# Connectors.net
KiCad netlist of a schematic drawn in Altium Designer
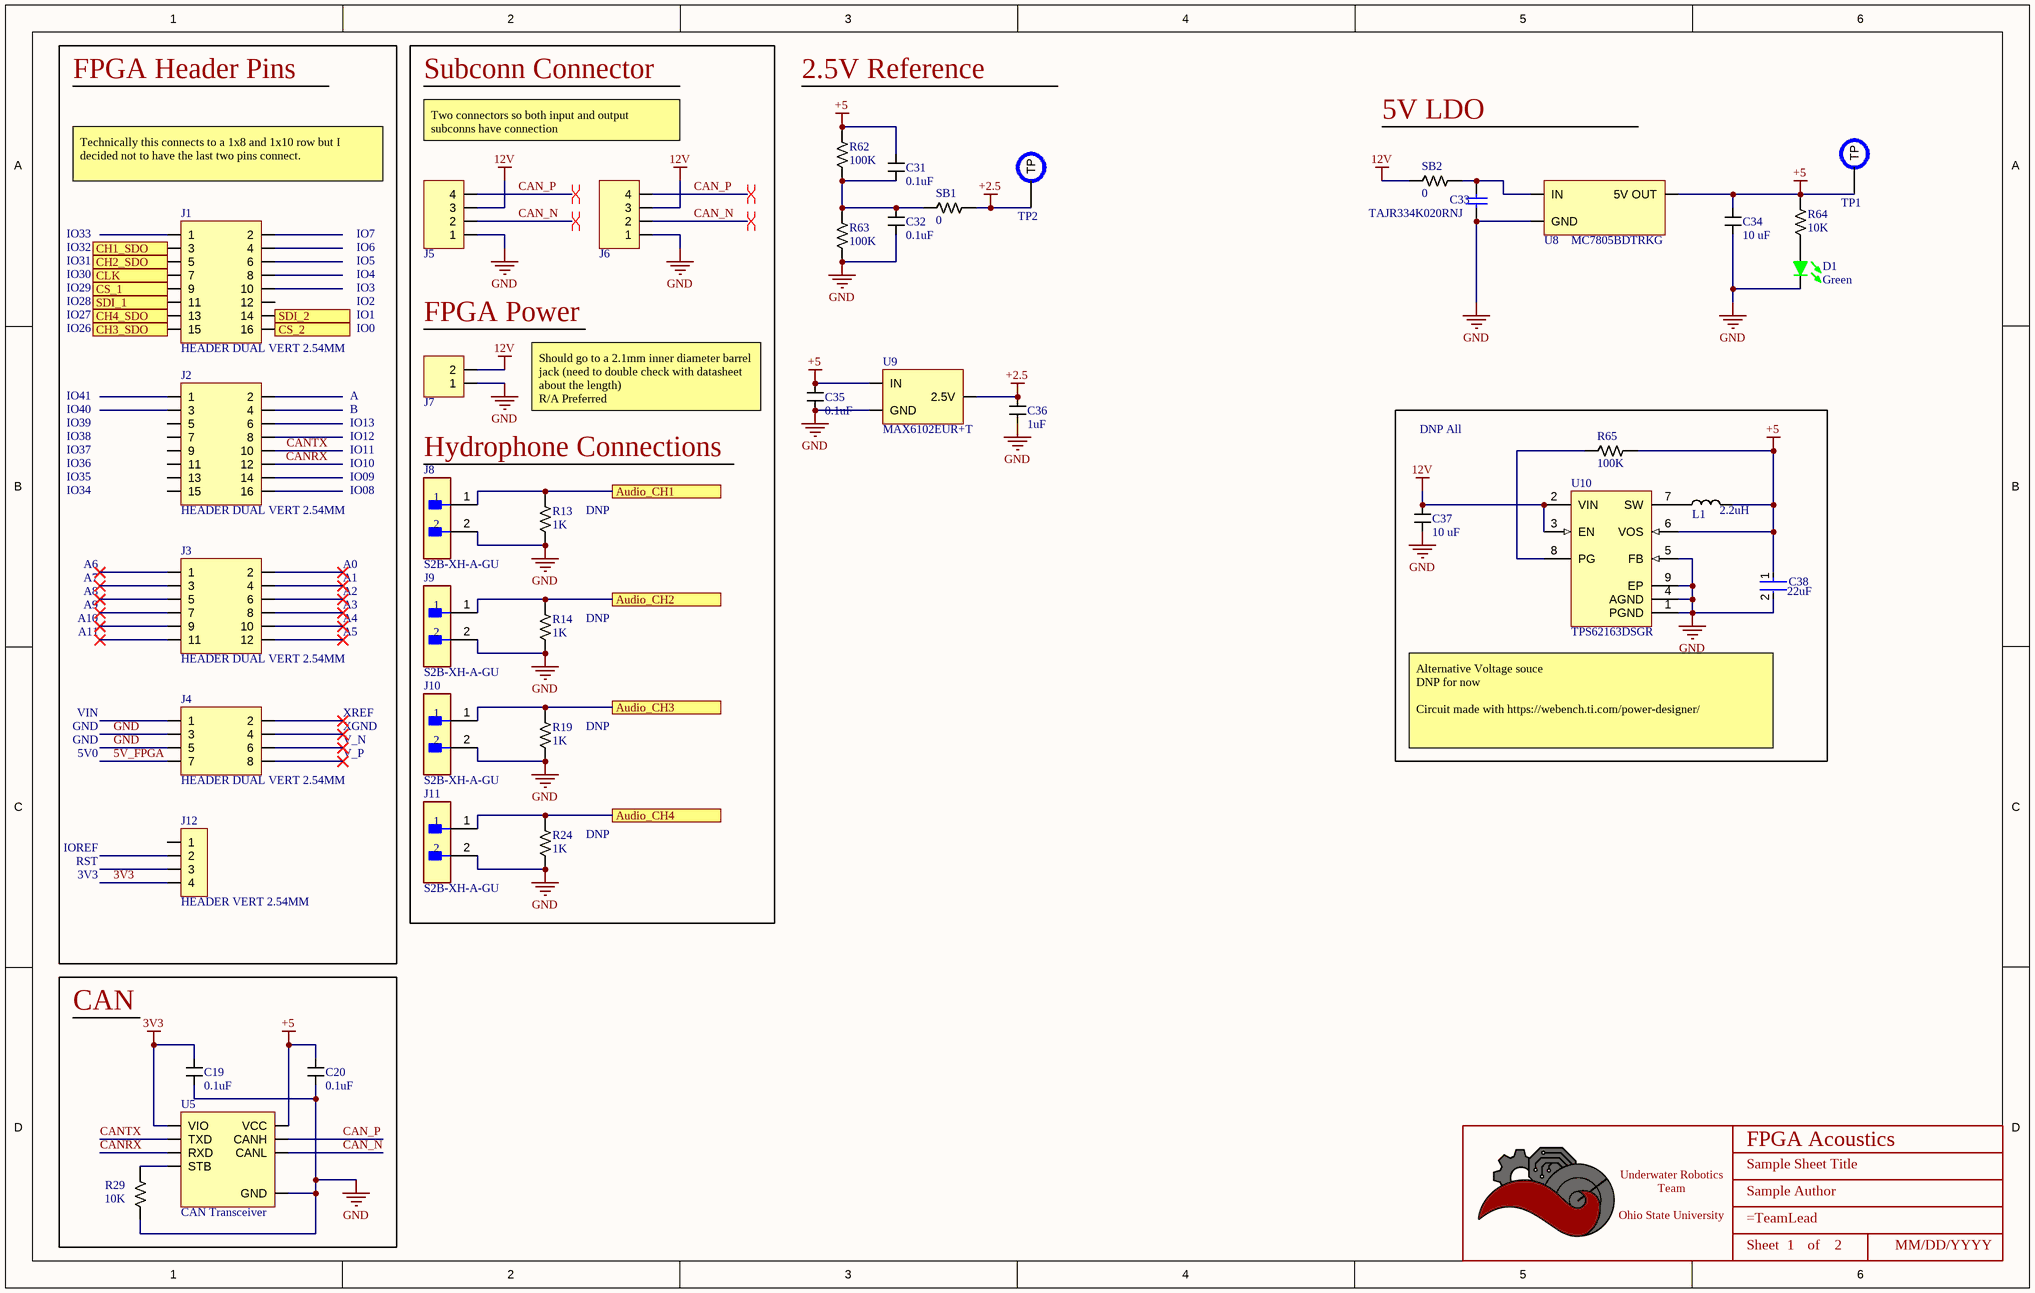
[diagram p0: Connectors.SchDoc]

(export (version "E")
  (design (tool "Eeschema 10.0.6"))
  (components
    (comp (ref "C19")
      (value "0.1uF")
      (footprint "CAPACITOR_0402")
      (description "Cap 100nF 25V +/-10%\r\nCeramic 0402")
      (fields
        (field (name "TOLERANCE") "+/- 10%")
        (field (name "VOLTAGE") "25V")
        (field (name "MADE BY") "Robert Pafford")
      )
      (libsource (lib "Capacitors") (part "CAPACITOR_0.1uF_0402"))
    )
    (comp (ref "C20")
      (value "0.1uF")
      (footprint "CAPACITOR_0402")
      (description "Cap 100nF 25V +/-10%\r\nCeramic 0402")
      (fields
        (field (name "TOLERANCE") "+/- 10%")
        (field (name "VOLTAGE") "25V")
        (field (name "MADE BY") "Robert Pafford")
      )
      (libsource (lib "Capacitors") (part "CAPACITOR_0.1uF_0402"))
    )
    (comp (ref "C31")
      (value "0.1uF")
      (footprint "CAPACITOR_0603")
      (description "Cap 100nF 6.3V +/-10%\r\nCeramic 0603")
      (fields
        (field (name "TOLERANCE") "+/- 10%")
        (field (name "VOLTAGE") "6.3V")
        (field (name "MADE BY") "Flip B")
      )
      (libsource (lib "Capacitors") (part "CAPACITOR_0.1uF_0603"))
    )
    (comp (ref "C32")
      (value "0.1uF")
      (footprint "CAPACITOR_0603")
      (description "Cap 100nF 6.3V +/-10%\r\nCeramic 0603")
      (fields
        (field (name "TOLERANCE") "+/- 10%")
        (field (name "VOLTAGE") "6.3V")
        (field (name "MADE BY") "Flip B")
      )
      (libsource (lib "Capacitors") (part "CAPACITOR_0.1uF_0603"))
    )
    (comp (ref "C33")
      (value "TAJR334K020RNJ")
      (footprint "CAPC2113X120X50NL20T30")
      (fields (field (name "MANUFACTURER") "AVX Interconnect / Elco"))
      (libsource (lib "Altium Content Vault") (part "CAP"))
    )
    (comp (ref "C34")
      (value "10uF Ceramic 6.3V")
      (footprint "CAPACITOR_0603")
      (description "Cap 10uF 6.3V +/-20%\r\nCeramic 0603")
      (fields
        (field (name "TOLERANCE") "+/- 20%")
        (field (name "VOLTAGE") "6.3V")
        (field (name "VALUE (UF)") "10 uF")
        (field (name "MADE BY") "Flip B")
      )
      (libsource (lib "Capacitors") (part "CAPACITOR_10uF_0603"))
    )
    (comp (ref "C35")
      (value "0.1uF")
      (footprint "CAPACITOR_0603")
      (description "Cap 100nF 25V +/-10%\r\nCeramic 0603")
      (fields
        (field (name "TOLERANCE") "+/- 10%")
        (field (name "VOLTAGE") "6.3V")
        (field (name "MADE BY") "Flip B")
      )
      (libsource (lib "Capacitors") (part "CAPACITOR_0.1uF_0603_25V"))
    )
    (comp (ref "C36")
      (value "1uF")
      (footprint "CAPACITOR_0603")
      (description "Cap 1uF 16V +/-10%\r\nCeramic 0603")
      (fields
        (field (name "TOLERANCE") "+/- 10%")
        (field (name "VOLTAGE") "16V")
        (field (name "MADE BY") "Flip B")
      )
      (libsource (lib "Capacitors") (part "CAPACITOR_1uF_0603"))
    )
    (comp (ref "C37")
      (value "10uF Ceramic 25V")
      (footprint "CAPACITOR_1206")
      (description "Cap 10uF 25V +/-10%\r\nCeramic 1206")
      (fields
        (field (name "TOLERANCE") "+/- 10%")
        (field (name "VOLTAGE") "25V")
        (field (name "VALUE (UF)") "10 uF")
        (field (name "MADE BY") "Robert Pafford")
      )
      (libsource (lib "Capacitors") (part "CAPACITOR_10uF_1206"))
    )
    (comp (ref "C38")
      (value "GRM31CR71A226KE15L")
      (footprint "FP-GRM31C-0_2-e0_3_0_8-MFG")
      (description "Chip Multilayer Ceramic Capacitors for General Purpose, 1206, 22uF, X7R, 15%, 10%, 10V")
      (fields
        (field (name "CAPACITANCE") "22uF")
        (field (name "VOLTAGE") "10V")
        (field (name "TOLERANCE") "10%")
      )
      (libsource (lib "Altium Content Vault") (part "02cd4be3c70576c341d710602a673aa"))
    )
    (comp (ref "D1")
      (value "150060GS75000")
      (footprint "LED_0603")
      (description "LED Green Vf= 3.2V If = 0.025A\r\n150060GS75000")
      (fields (field (name "COLOR") "Green") (field (name "MADE BY") "Flip B"))
      (libsource (lib "Diodes") (part "LED_Green_0603_3.2V"))
    )
    (comp (ref "J1")
      (value "HEADER DUAL VERT 2.54MM")
      (footprint "HEADER_2x8PIN_2.54mm")
      (description "CONN HEADER VERT 8POS 2.54MM")
      (fields (field (name "CREATED BY") "John Ulm"))
      (libsource (lib "Connectors") (part "HEADER_2x8PIN_2.54_1"))
    )
    (comp (ref "J2")
      (value "HEADER DUAL VERT 2.54MM")
      (footprint "HEADER_2x8PIN_2.54mm")
      (description "CONN HEADER VERT 8POS 2.54MM")
      (fields (field (name "CREATED BY") "John Ulm"))
      (libsource (lib "Connectors") (part "HEADER_2x8PIN_2.54_1"))
    )
    (comp (ref "J3")
      (value "HEADER DUAL VERT 2.54MM")
      (footprint "HEADER_2x6PIN_2.54mm")
      (description "CONN HEADER VERT 6POS 2.54MM")
      (fields (field (name "CREATED BY") "John Ulm"))
      (libsource (lib "Connectors") (part "HEADER_2x6PIN_2.54"))
    )
    (comp (ref "J4")
      (value "HEADER DUAL VERT 2.54MM")
      (footprint "HEADER_2x4PIN_2.54mm")
      (description "CONN HEADER VERT 4POS 2.54MM")
      (fields (field (name "CREATED BY") "John Ulm"))
      (libsource (lib "Connectors") (part "HEADER_2x4PIN_2.54_1"))
    )
    (comp (ref "J5")
      (value "Microfit+ R/A")
      (footprint "CONN_MOLEX_MICROFIT+_4_POS_R/A - duplicate")
      (description "Molex Microfit+ \r\n212528 4 POS R/A Black")
      (fields (field (name "MANUFACTURER") "Molex"))
      (libsource (lib "Connectors") (part "CONN_MOLEX_MICROFIT+_4POS_R/A"))
    )
    (comp (ref "J6")
      (value "Microfit+ R/A")
      (footprint "CONN_MOLEX_MICROFIT+_4_POS_R/A - duplicate")
      (description "Molex Microfit+ \r\n212528 4 POS R/A Black")
      (fields (field (name "MANUFACTURER") "Molex"))
      (libsource (lib "Connectors") (part "CONN_MOLEX_MICROFIT+_4POS_R/A"))
    )
    (comp (ref "J7")
      (value "Microfit+ R/A")
      (footprint "CONN_MOLEX_MICROFIT+_2Flat_POS_R/A")
      (description "Molex Microfit+ \r\n2157601002 2POS Right Angle")
      (fields (field (name "MANUFACTURER") "Molex"))
      (libsource (lib "Connectors") (part "CONN_MOLEX_MICROFIT+_2POS_Flat_R/A"))
    )
    (comp (ref "J8")
      (value "S2B-XH-A-GU")
      (footprint "FP-S2B-XH-A-GU-MFG")
      (description "Conn Shrouded Header HDR 2 POS 2.45mm Solder ST Top Entry Thru-Hole")
      (libsource (lib "Altium Content Vault") (part "3bc925449376181038e59eaffc5286c"))
    )
    (comp (ref "J9")
      (value "S2B-XH-A-GU")
      (footprint "FP-S2B-XH-A-GU-MFG")
      (description "Conn Shrouded Header HDR 2 POS 2.45mm Solder ST Top Entry Thru-Hole")
      (libsource (lib "Altium Content Vault") (part "3bc925449376181038e59eaffc5286c"))
    )
    (comp (ref "J10")
      (value "S2B-XH-A-GU")
      (footprint "FP-S2B-XH-A-GU-MFG")
      (description "Conn Shrouded Header HDR 2 POS 2.45mm Solder ST Top Entry Thru-Hole")
      (libsource (lib "Altium Content Vault") (part "3bc925449376181038e59eaffc5286c"))
    )
    (comp (ref "J11")
      (value "S2B-XH-A-GU")
      (footprint "FP-S2B-XH-A-GU-MFG")
      (description "Conn Shrouded Header HDR 2 POS 2.45mm Solder ST Top Entry Thru-Hole")
      (libsource (lib "Altium Content Vault") (part "3bc925449376181038e59eaffc5286c"))
    )
    (comp (ref "J12")
      (value "HEADER VERT 2.54MM")
      (footprint "HEADER_4PIN_2.54MM")
      (description "CONN HEADER VERT 4POS 2.54MM")
      (fields (field (name "MADE BY") "Robert Pafford"))
      (libsource (lib "Connectors") (part "HEADER_4PIN_2.54MM"))
    )
    (comp (ref "L1")
      (value "2.2uH")
      (footprint "PA4332.222NLT")
      (description "2.2 µH Shielded Drum Core, Wirewound Inductor 4.3 A 48mOhm Max Nonstandard")
      (fields (field (name "Comment") "2.2uH Shielded"))
      (libsource (lib "Inductors") (part "INDUCTOR_2.2uH"))
    )
    (comp (ref "R13")
      (value "1k Ohm 1% 1/16W")
      (footprint "RESISTOR_0402")
      (description "RES 1k OHM 1% 1/16W 0402")
      (fields
        (field (name "TOLERANCE") "+/- 1%")
        (field (name "VALUE  (OHMS)") "1K")
        (field (name "MADE BY") "Robert Pafford")
      )
      (libsource (lib "Resistors") (part "RESISTOR_1K_0402"))
    )
    (comp (ref "R14")
      (value "1k Ohm 1% 1/16W")
      (footprint "RESISTOR_0402")
      (description "RES 1k OHM 1% 1/16W 0402")
      (fields
        (field (name "TOLERANCE") "+/- 1%")
        (field (name "VALUE  (OHMS)") "1K")
        (field (name "MADE BY") "Robert Pafford")
      )
      (libsource (lib "Resistors") (part "RESISTOR_1K_0402"))
    )
    (comp (ref "R19")
      (value "1k Ohm 1% 1/16W")
      (footprint "RESISTOR_0402")
      (description "RES 1k OHM 1% 1/16W 0402")
      (fields
        (field (name "TOLERANCE") "+/- 1%")
        (field (name "VALUE  (OHMS)") "1K")
        (field (name "MADE BY") "Robert Pafford")
      )
      (libsource (lib "Resistors") (part "RESISTOR_1K_0402"))
    )
    (comp (ref "R24")
      (value "1k Ohm 1% 1/16W")
      (footprint "RESISTOR_0402")
      (description "RES 1k OHM 1% 1/16W 0402")
      (fields
        (field (name "TOLERANCE") "+/- 1%")
        (field (name "VALUE  (OHMS)") "1K")
        (field (name "MADE BY") "Robert Pafford")
      )
      (libsource (lib "Resistors") (part "RESISTOR_1K_0402"))
    )
    (comp (ref "R29")
      (value "10k Ohm 1% 1/16W")
      (footprint "RESISTOR_0402")
      (description "RES 10k OHM 1% 1/16W 0402")
      (fields
        (field (name "TOLERANCE") "+/- 1%")
        (field (name "VALUE  (OHMS)") "10K")
        (field (name "MADE BY") "Robert Pafford")
      )
      (libsource (lib "Resistors") (part "RESISTOR_10K_0402"))
    )
    (comp (ref "R62")
      (value "100k Ohm 0.5% 1/10W")
      (footprint "RESISTOR_0603")
      (description "RES 100k OHM 0.5% 1/10W 0603")
      (fields
        (field (name "TOLERANCE") "+/- 0.5%")
        (field (name "VALUE  (OHMS)") "100K")
        (field (name "MADE BY") "John Ulm")
      )
      (libsource (lib "Resistors") (part "RESISTOR_100K_0.5%_0603"))
    )
    (comp (ref "R63")
      (value "100k Ohm 0.5% 1/10W")
      (footprint "RESISTOR_0603")
      (description "RES 100k OHM 0.5% 1/10W 0603")
      (fields
        (field (name "TOLERANCE") "+/- 0.5%")
        (field (name "VALUE  (OHMS)") "100K")
        (field (name "MADE BY") "John Ulm")
      )
      (libsource (lib "Resistors") (part "RESISTOR_100K_0.5%_0603"))
    )
    (comp (ref "R64")
      (value "10k Ohm 5% 1/10W")
      (footprint "RESISTOR_0603")
      (description "RES 10k OHM 5% 1/10W 0603")
      (fields
        (field (name "TOLERANCE") "+/- 5%")
        (field (name "VALUE  (OHMS)") "10K")
        (field (name "MADE BY") "Robert Pafford")
      )
      (libsource (lib "Resistors") (part "RESISTOR_10K_0603"))
    )
    (comp (ref "R65")
      (value "100k Ohm 1% 1/16W")
      (footprint "RESISTOR_0402")
      (description "RES 100k OHM 1% 1/16W 0402")
      (fields
        (field (name "TOLERANCE") "+/- 1%")
        (field (name "VALUE  (OHMS)") "100K")
        (field (name "MADE BY") "Robert Pafford")
      )
      (libsource (lib "Resistors") (part "RESISTOR_100K_0402"))
    )
    (comp (ref "SB1")
      (value "0 Ohm Jumper No Fit")
      (footprint "RESISTOR_0603")
      (description "0 Ohm Jumper No Fit for Solder Bridge")
      (fields (field (name "VALUE  (OHMS)") "0") (field (name "MADE BY") "Robert Pafford"))
      (libsource (lib "Resistors") (part "JUMPER_0_0603"))
    )
    (comp (ref "SB2")
      (value "0")
      (footprint "RESISTOR_1206")
      (description "JUMPER 0OHM 1206")
      (fields (field (name "Comment") "JUMPER_0_1206"))
      (libsource (lib "Resistors") (part "JUMPER_0_1206"))
    )
    (comp (ref "TP1")
      (value "PCB Test Point")
      (footprint "TESTPOINT_1.2MM")
      (fields (field (name "MADE BY") "Robert Pafford"))
      (libsource (lib "Connectors") (part "TESTPOINT"))
    )
    (comp (ref "TP2")
      (value "PCB Test Point")
      (footprint "TESTPOINT_1.2MM")
      (fields (field (name "MADE BY") "Robert Pafford"))
      (libsource (lib "Connectors") (part "TESTPOINT"))
    )
    (comp (ref "U5")
      (value "CAN Transceiver")
      (footprint "SOIC-8")
      (description "CAN Interface IC High-Speed CAN Transceiver with Standby Mode")
      (fields (field (name "MADE BY") "Robert Pafford"))
      (libsource (lib "Integrated Circuits") (part "TJA1442AT"))
    )
    (comp (ref "U8")
      (value "MC7805BDTRKG")
      (footprint "DPAK-2")
      (description "Linear Voltage Regulator IC Positive Fixed 1 Output 1A DPAK")
      (libsource (lib "Integrated Circuits") (part "MC7805BDTRKG"))
    )
    (comp (ref "U9")
      (value "MAX6102EUR+T")
      (footprint "SOT-23-3")
      (description "Series Voltage Reference IC Fixed 2.5V V ±0.4% 5 mA SOT-23-3")
      (libsource (lib "Integrated Circuits") (part "MAX6102EUR+T"))
    )
    (comp (ref "U10")
      (value "TPS62163DSGR")
      (footprint "DSG0008A_V")
      (fields (field (name "MANUFACTURER") "Texas Instruments"))
      (libsource (lib "Altium Content Vault") (part "TI-TPS62163DSG8-1600X900TP"))
    )
  )
  (nets
    (net (code "1") (name "+2.5") (class "Default")
      (node (ref "C36") (pin "1") (pinfunction "1_1") (pintype "passive"))
      (node (ref "SB1") (pin "1") (pinfunction "1_1") (pintype "passive"))
      (node (ref "TP2") (pin "TP") (pinfunction "TP_TP") (pintype "passive"))
      (node (ref "U9") (pin "2") (pinfunction "2.5V_2") (pintype "passive"))
    )
    (net (code "2") (name "+5") (class "Default")
      (node (ref "C20") (pin "1") (pinfunction "1_1") (pintype "passive"))
      (node (ref "C31") (pin "1") (pinfunction "1_1") (pintype "passive"))
      (node (ref "C34") (pin "1") (pinfunction "1_1") (pintype "passive"))
      (node (ref "C35") (pin "1") (pinfunction "1_1") (pintype "passive"))
      (node (ref "C38") (pin "1") (pinfunction "1_1") (pintype "passive"))
      (node (ref "L1") (pin "1") (pinfunction "1_1") (pintype "passive"))
      (node (ref "R62") (pin "1") (pinfunction "1_1") (pintype "passive"))
      (node (ref "R64") (pin "1") (pinfunction "1_1") (pintype "passive"))
      (node (ref "R65") (pin "1") (pinfunction "1_1") (pintype "passive"))
      (node (ref "TP1") (pin "TP") (pinfunction "TP_TP") (pintype "passive"))
      (node (ref "U10") (pin "6") (pinfunction "VOS_6") (pintype "input"))
      (node (ref "U5") (pin "3") (pinfunction "VCC_3") (pintype "passive"))
      (node (ref "U8") (pin "3") (pinfunction "5V_OUT_3") (pintype "passive"))
      (node (ref "U9") (pin "1") (pinfunction "IN_1") (pintype "passive"))
    )
    (net (code "3") (name "/5V_FPGA") (class "Default")
      (node (ref "J4") (pin "7") (pinfunction "7_7") (pintype "passive"))
    )
    (net (code "4") (name "/Audio_CH1") (class "Default")
      (node (ref "J8") (pin "1") (pinfunction "1_1") (pintype "passive"))
      (node (ref "R13") (pin "1") (pinfunction "1_1") (pintype "passive"))
    )
    (net (code "5") (name "/Audio_CH2") (class "Default")
      (node (ref "J9") (pin "1") (pinfunction "1_1") (pintype "passive"))
      (node (ref "R14") (pin "1") (pinfunction "1_1") (pintype "passive"))
    )
    (net (code "6") (name "/Audio_CH3") (class "Default")
      (node (ref "J10") (pin "1") (pinfunction "1_1") (pintype "passive"))
      (node (ref "R19") (pin "1") (pinfunction "1_1") (pintype "passive"))
    )
    (net (code "7") (name "/Audio_CH4") (class "Default")
      (node (ref "J11") (pin "1") (pinfunction "1_1") (pintype "passive"))
      (node (ref "R24") (pin "1") (pinfunction "1_1") (pintype "passive"))
    )
    (net (code "8") (name "/CANRX") (class "Default")
      (node (ref "J2") (pin "12") (pinfunction "12_12") (pintype "passive"))
      (node (ref "U5") (pin "4") (pinfunction "RXD_4") (pintype "passive"))
    )
    (net (code "9") (name "/CANTX") (class "Default")
      (node (ref "J2") (pin "10") (pinfunction "10_10") (pintype "passive"))
      (node (ref "U5") (pin "1") (pinfunction "TXD_1") (pintype "passive"))
    )
    (net (code "10") (name "/CAN_N") (class "Default")
      (node (ref "J5") (pin "2") (pinfunction "2_2") (pintype "passive"))
      (node (ref "J6") (pin "2") (pinfunction "2_2") (pintype "passive"))
      (node (ref "U5") (pin "6") (pinfunction "CANL_6") (pintype "passive"))
    )
    (net (code "11") (name "/CAN_P") (class "Default")
      (node (ref "J5") (pin "4") (pinfunction "4_4") (pintype "passive"))
      (node (ref "J6") (pin "4") (pinfunction "4_4") (pintype "passive"))
      (node (ref "U5") (pin "7") (pinfunction "CANH_7") (pintype "passive"))
    )
    (net (code "12") (name "/CH1_SDO") (class "Default")
      (node (ref "J1") (pin "3") (pinfunction "3_3") (pintype "passive"))
    )
    (net (code "13") (name "/CH2_SDO") (class "Default")
      (node (ref "J1") (pin "5") (pinfunction "5_5") (pintype "passive"))
    )
    (net (code "14") (name "/CH3_SDO") (class "Default")
      (node (ref "J1") (pin "15") (pinfunction "15_15") (pintype "passive"))
    )
    (net (code "15") (name "/CH4_SDO") (class "Default")
      (node (ref "J1") (pin "13") (pinfunction "13_13") (pintype "passive"))
    )
    (net (code "16") (name "/CLK") (class "Default")
      (node (ref "J1") (pin "7") (pinfunction "7_7") (pintype "passive"))
    )
    (net (code "17") (name "/CS_1") (class "Default")
      (node (ref "J1") (pin "9") (pinfunction "9_9") (pintype "passive"))
    )
    (net (code "18") (name "/CS_2") (class "Default")
      (node (ref "J1") (pin "16") (pinfunction "16_16") (pintype "passive"))
    )
    (net (code "19") (name "/SDI_1") (class "Default")
      (node (ref "J1") (pin "11") (pinfunction "11_11") (pintype "passive"))
    )
    (net (code "20") (name "/SDI_2") (class "Default")
      (node (ref "J1") (pin "14") (pinfunction "14_14") (pintype "passive"))
    )
    (net (code "21") (name "3V3") (class "Default")
      (node (ref "C19") (pin "1") (pinfunction "1_1") (pintype "passive"))
      (node (ref "J12") (pin "4") (pinfunction "4_4") (pintype "passive"))
      (node (ref "U5") (pin "5") (pinfunction "VIO_5") (pintype "passive"))
    )
    (net (code "22") (name "12V") (class "Default")
      (node (ref "C37") (pin "1") (pinfunction "1_1") (pintype "passive"))
      (node (ref "J5") (pin "3") (pinfunction "3_3") (pintype "passive"))
      (node (ref "J6") (pin "3") (pinfunction "3_3") (pintype "passive"))
      (node (ref "J7") (pin "2") (pinfunction "2_2") (pintype "passive"))
      (node (ref "SB2") (pin "2") (pinfunction "2_2") (pintype "passive"))
      (node (ref "U10") (pin "2") (pinfunction "VIN_2") (pintype "power_in"))
      (node (ref "U10") (pin "3") (pinfunction "EN_3") (pintype "input"))
    )
    (net (code "23") (name "GND") (class "Default")
      (node (ref "C19") (pin "2") (pinfunction "2_2") (pintype "passive"))
      (node (ref "C20") (pin "2") (pinfunction "2_2") (pintype "passive"))
      (node (ref "C32") (pin "2") (pinfunction "2_2") (pintype "passive"))
      (node (ref "C33") (pin "1") (pinfunction "1_1") (pintype "passive"))
      (node (ref "C34") (pin "2") (pinfunction "2_2") (pintype "passive"))
      (node (ref "C35") (pin "2") (pinfunction "2_2") (pintype "passive"))
      (node (ref "C36") (pin "2") (pinfunction "2_2") (pintype "passive"))
      (node (ref "C37") (pin "2") (pinfunction "2_2") (pintype "passive"))
      (node (ref "C38") (pin "2") (pinfunction "2_2") (pintype "passive"))
      (node (ref "D1") (pin "2") (pinfunction "2_2") (pintype "passive"))
      (node (ref "J10") (pin "2") (pinfunction "2_2") (pintype "passive"))
      (node (ref "J11") (pin "2") (pinfunction "2_2") (pintype "passive"))
      (node (ref "J4") (pin "3") (pinfunction "3_3") (pintype "passive"))
      (node (ref "J4") (pin "5") (pinfunction "5_5") (pintype "passive"))
      (node (ref "J5") (pin "1") (pinfunction "1_1") (pintype "passive"))
      (node (ref "J6") (pin "1") (pinfunction "1_1") (pintype "passive"))
      (node (ref "J7") (pin "1") (pinfunction "1_1") (pintype "passive"))
      (node (ref "J8") (pin "2") (pinfunction "2_2") (pintype "passive"))
      (node (ref "J9") (pin "2") (pinfunction "2_2") (pintype "passive"))
      (node (ref "R13") (pin "2") (pinfunction "2_2") (pintype "passive"))
      (node (ref "R14") (pin "2") (pinfunction "2_2") (pintype "passive"))
      (node (ref "R19") (pin "2") (pinfunction "2_2") (pintype "passive"))
      (node (ref "R24") (pin "2") (pinfunction "2_2") (pintype "passive"))
      (node (ref "R29") (pin "2") (pinfunction "2_2") (pintype "passive"))
      (node (ref "R63") (pin "2") (pinfunction "2_2") (pintype "passive"))
      (node (ref "U10") (pin "1") (pinfunction "PGND_1") (pintype "power_in"))
      (node (ref "U10") (pin "4") (pinfunction "AGND_4") (pintype "power_in"))
      (node (ref "U10") (pin "5") (pinfunction "FB_5") (pintype "input"))
      (node (ref "U10") (pin "9") (pinfunction "EP_9") (pintype "power_in"))
      (node (ref "U5") (pin "2") (pinfunction "GND_2") (pintype "passive"))
      (node (ref "U8") (pin "2") (pinfunction "GND_2") (pintype "passive"))
      (node (ref "U9") (pin "3") (pinfunction "GND_3") (pintype "passive"))
    )
    (net (code "24") (name "Net-(C31-Pad2)") (class "Default")
      (node (ref "C31") (pin "2") (pinfunction "2_2") (pintype "passive"))
      (node (ref "C32") (pin "1") (pinfunction "1_1") (pintype "passive"))
      (node (ref "R62") (pin "2") (pinfunction "2_2") (pintype "passive"))
      (node (ref "R63") (pin "1") (pinfunction "1_1") (pintype "passive"))
      (node (ref "SB1") (pin "2") (pinfunction "2_2") (pintype "passive"))
    )
    (net (code "25") (name "Net-(D1-Pad1)") (class "Default")
      (node (ref "D1") (pin "1") (pinfunction "1_1") (pintype "passive"))
      (node (ref "R64") (pin "2") (pinfunction "2_2") (pintype "passive"))
    )
    (net (code "26") (name "Net-(U5-STB)") (class "Default")
      (node (ref "R29") (pin "1") (pinfunction "1_1") (pintype "passive"))
      (node (ref "U5") (pin "8") (pinfunction "STB_8") (pintype "passive"))
    )
    (net (code "27") (name "Net-(U8-IN)") (class "Default")
      (node (ref "C33") (pin "2") (pinfunction "2_2") (pintype "passive"))
      (node (ref "SB2") (pin "1") (pinfunction "1_1") (pintype "passive"))
      (node (ref "U8") (pin "1") (pinfunction "IN_1") (pintype "passive"))
    )
    (net (code "28") (name "Net-(U10-PG)") (class "Default")
      (node (ref "R65") (pin "2") (pinfunction "2_2") (pintype "passive"))
      (node (ref "U10") (pin "8") (pinfunction "PG_8") (pintype "tri_state"))
    )
    (net (code "29") (name "Net-(U10-SW)") (class "Default")
      (node (ref "L1") (pin "2") (pinfunction "2_2") (pintype "passive"))
      (node (ref "U10") (pin "7") (pinfunction "SW_7") (pintype "power_in"))
    )
    (net (code "30") (name "unconnected-(J1-Pad1)") (class "Default")
      (node (ref "J1") (pin "1") (pinfunction "1_1") (pintype "passive"))
    )
    (net (code "31") (name "unconnected-(J1-Pad2)") (class "Default")
      (node (ref "J1") (pin "2") (pinfunction "2_2") (pintype "passive"))
    )
    (net (code "32") (name "unconnected-(J1-Pad4)") (class "Default")
      (node (ref "J1") (pin "4") (pinfunction "4_4") (pintype "passive"))
    )
    (net (code "33") (name "unconnected-(J1-Pad6)") (class "Default")
      (node (ref "J1") (pin "6") (pinfunction "6_6") (pintype "passive"))
    )
    (net (code "34") (name "unconnected-(J1-Pad8)") (class "Default")
      (node (ref "J1") (pin "8") (pinfunction "8_8") (pintype "passive"))
    )
    (net (code "35") (name "unconnected-(J1-Pad10)") (class "Default")
      (node (ref "J1") (pin "10") (pinfunction "10_10") (pintype "passive"))
    )
    (net (code "36") (name "unconnected-(J1-Pad12)") (class "Default")
      (node (ref "J1") (pin "12") (pinfunction "12_12") (pintype "passive"))
    )
    (net (code "37") (name "unconnected-(J2-Pad1)") (class "Default")
      (node (ref "J2") (pin "1") (pinfunction "1_1") (pintype "passive"))
    )
    (net (code "38") (name "unconnected-(J2-Pad2)") (class "Default")
      (node (ref "J2") (pin "2") (pinfunction "2_2") (pintype "passive"))
    )
    (net (code "39") (name "unconnected-(J2-Pad3)") (class "Default")
      (node (ref "J2") (pin "3") (pinfunction "3_3") (pintype "passive"))
    )
    (net (code "40") (name "unconnected-(J2-Pad4)") (class "Default")
      (node (ref "J2") (pin "4") (pinfunction "4_4") (pintype "passive"))
    )
    (net (code "41") (name "unconnected-(J2-Pad5)") (class "Default")
      (node (ref "J2") (pin "5") (pinfunction "5_5") (pintype "passive"))
    )
    (net (code "42") (name "unconnected-(J2-Pad6)") (class "Default")
      (node (ref "J2") (pin "6") (pinfunction "6_6") (pintype "passive"))
    )
    (net (code "43") (name "unconnected-(J2-Pad7)") (class "Default")
      (node (ref "J2") (pin "7") (pinfunction "7_7") (pintype "passive"))
    )
    (net (code "44") (name "unconnected-(J2-Pad8)") (class "Default")
      (node (ref "J2") (pin "8") (pinfunction "8_8") (pintype "passive"))
    )
    (net (code "45") (name "unconnected-(J2-Pad9)") (class "Default")
      (node (ref "J2") (pin "9") (pinfunction "9_9") (pintype "passive"))
    )
    (net (code "46") (name "unconnected-(J2-Pad11)") (class "Default")
      (node (ref "J2") (pin "11") (pinfunction "11_11") (pintype "passive"))
    )
    (net (code "47") (name "unconnected-(J2-Pad13)") (class "Default")
      (node (ref "J2") (pin "13") (pinfunction "13_13") (pintype "passive"))
    )
    (net (code "48") (name "unconnected-(J2-Pad14)") (class "Default")
      (node (ref "J2") (pin "14") (pinfunction "14_14") (pintype "passive"))
    )
    (net (code "49") (name "unconnected-(J2-Pad15)") (class "Default")
      (node (ref "J2") (pin "15") (pinfunction "15_15") (pintype "passive"))
    )
    (net (code "50") (name "unconnected-(J2-Pad16)") (class "Default")
      (node (ref "J2") (pin "16") (pinfunction "16_16") (pintype "passive"))
    )
    (net (code "51") (name "unconnected-(J3-Pad1)") (class "Default")
      (node (ref "J3") (pin "1") (pinfunction "1_1") (pintype "passive+no_connect"))
    )
    (net (code "52") (name "unconnected-(J3-Pad2)") (class "Default")
      (node (ref "J3") (pin "2") (pinfunction "2_2") (pintype "passive+no_connect"))
    )
    (net (code "53") (name "unconnected-(J3-Pad3)") (class "Default")
      (node (ref "J3") (pin "3") (pinfunction "3_3") (pintype "passive+no_connect"))
    )
    (net (code "54") (name "unconnected-(J3-Pad4)") (class "Default")
      (node (ref "J3") (pin "4") (pinfunction "4_4") (pintype "passive+no_connect"))
    )
    (net (code "55") (name "unconnected-(J3-Pad5)") (class "Default")
      (node (ref "J3") (pin "5") (pinfunction "5_5") (pintype "passive+no_connect"))
    )
    (net (code "56") (name "unconnected-(J3-Pad6)") (class "Default")
      (node (ref "J3") (pin "6") (pinfunction "6_6") (pintype "passive+no_connect"))
    )
    (net (code "57") (name "unconnected-(J3-Pad7)") (class "Default")
      (node (ref "J3") (pin "7") (pinfunction "7_7") (pintype "passive+no_connect"))
    )
    (net (code "58") (name "unconnected-(J3-Pad8)") (class "Default")
      (node (ref "J3") (pin "8") (pinfunction "8_8") (pintype "passive+no_connect"))
    )
    (net (code "59") (name "unconnected-(J3-Pad9)") (class "Default")
      (node (ref "J3") (pin "9") (pinfunction "9_9") (pintype "passive+no_connect"))
    )
    (net (code "60") (name "unconnected-(J3-Pad10)") (class "Default")
      (node (ref "J3") (pin "10") (pinfunction "10_10") (pintype "passive+no_connect"))
    )
    (net (code "61") (name "unconnected-(J3-Pad11)") (class "Default")
      (node (ref "J3") (pin "11") (pinfunction "11_11") (pintype "passive+no_connect"))
    )
    (net (code "62") (name "unconnected-(J3-Pad12)") (class "Default")
      (node (ref "J3") (pin "12") (pinfunction "12_12") (pintype "passive+no_connect"))
    )
    (net (code "63") (name "unconnected-(J4-Pad1)") (class "Default")
      (node (ref "J4") (pin "1") (pinfunction "1_1") (pintype "passive"))
    )
    (net (code "64") (name "unconnected-(J4-Pad2)") (class "Default")
      (node (ref "J4") (pin "2") (pinfunction "2_2") (pintype "passive+no_connect"))
    )
    (net (code "65") (name "unconnected-(J4-Pad4)") (class "Default")
      (node (ref "J4") (pin "4") (pinfunction "4_4") (pintype "passive+no_connect"))
    )
    (net (code "66") (name "unconnected-(J4-Pad6)") (class "Default")
      (node (ref "J4") (pin "6") (pinfunction "6_6") (pintype "passive+no_connect"))
    )
    (net (code "67") (name "unconnected-(J4-Pad8)") (class "Default")
      (node (ref "J4") (pin "8") (pinfunction "8_8") (pintype "passive+no_connect"))
    )
    (net (code "68") (name "unconnected-(J12-Pad1)") (class "Default")
      (node (ref "J12") (pin "1") (pinfunction "1_1") (pintype "passive"))
    )
    (net (code "69") (name "unconnected-(J12-Pad2)") (class "Default")
      (node (ref "J12") (pin "2") (pinfunction "2_2") (pintype "passive"))
    )
    (net (code "70") (name "unconnected-(J12-Pad3)") (class "Default")
      (node (ref "J12") (pin "3") (pinfunction "3_3") (pintype "passive"))
    )
  )
)
